# final_project3.net
KiCad netlist of a schematic drawn in EAGLE
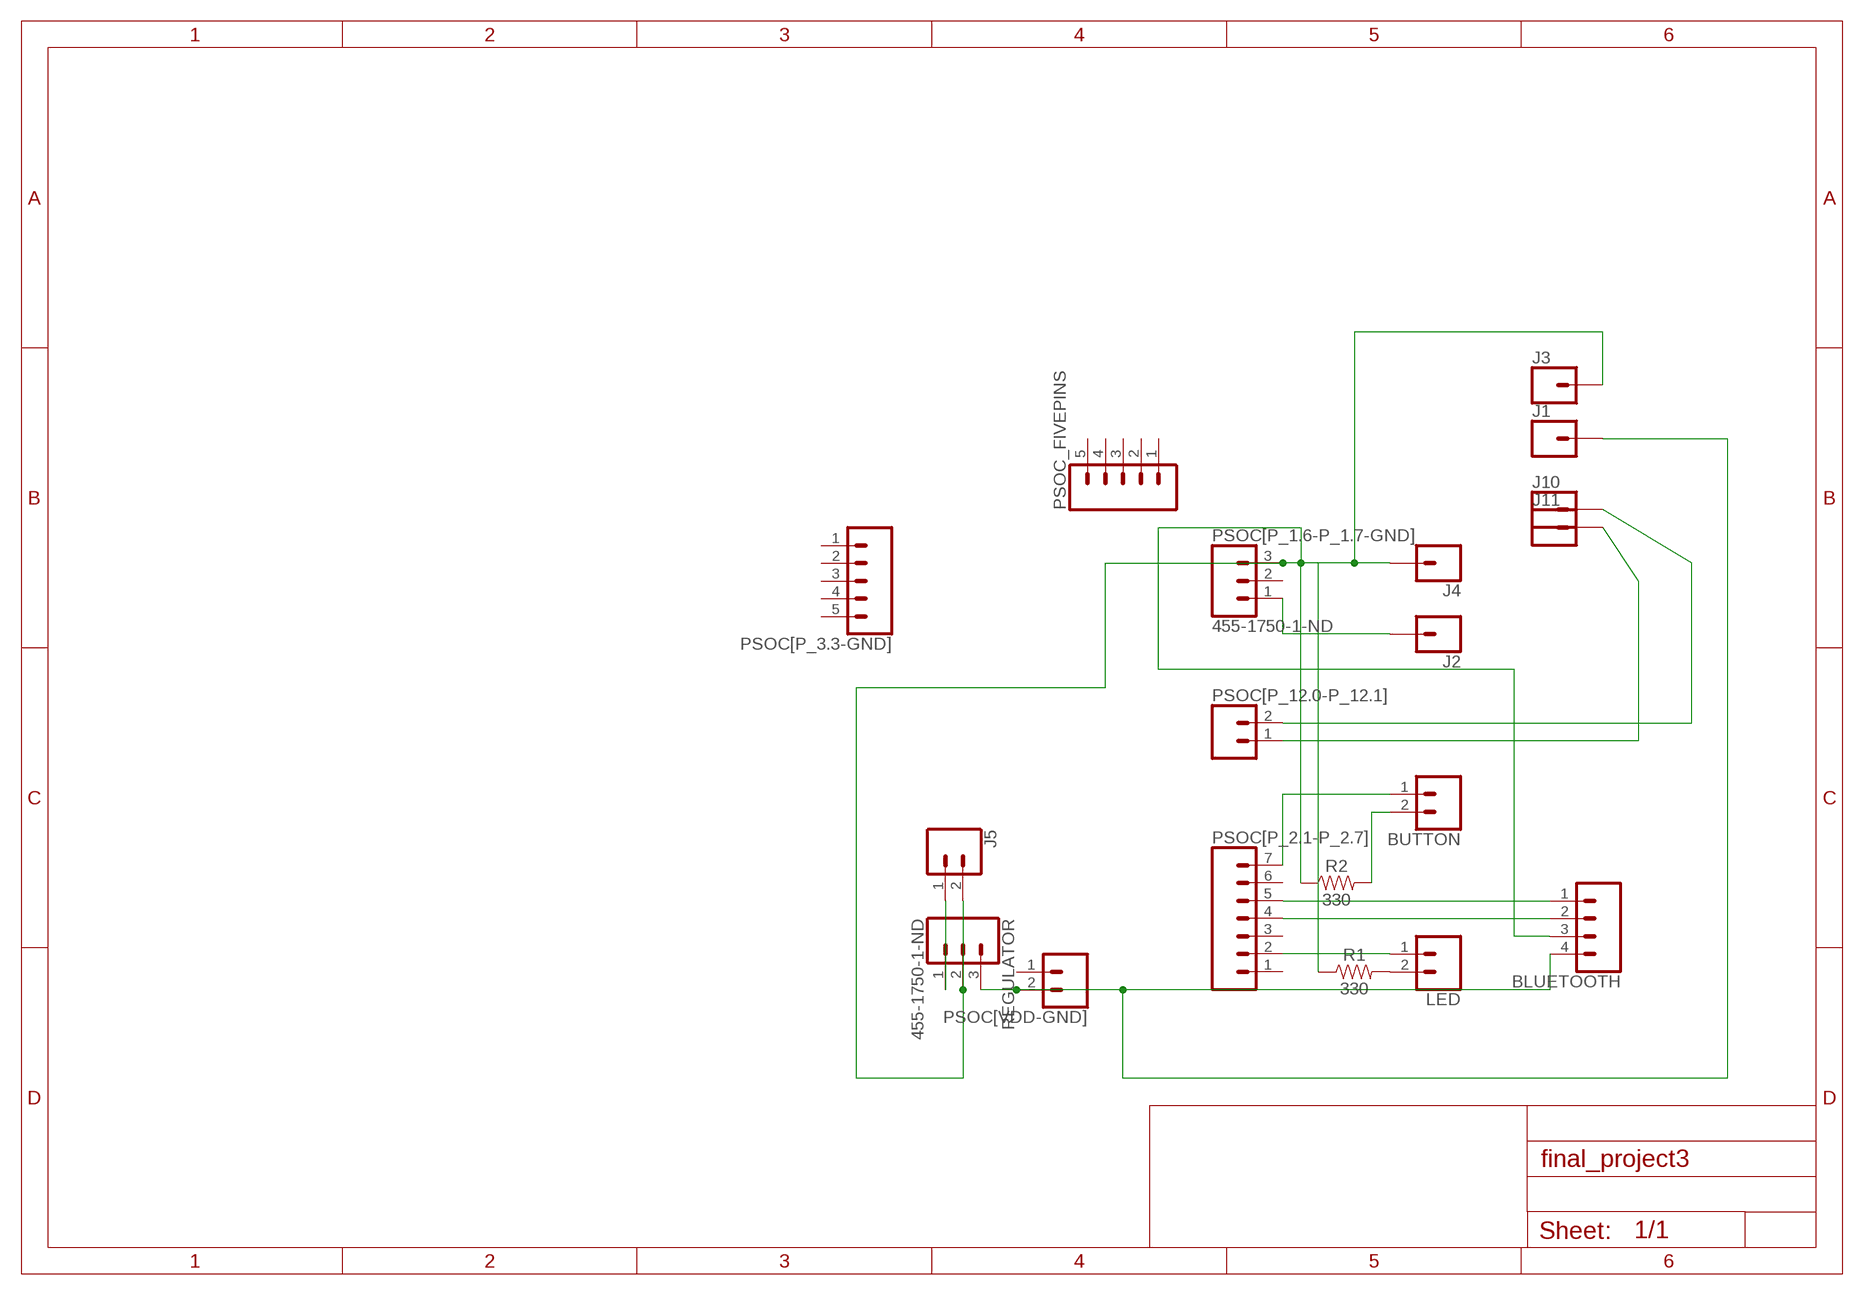
[diagram p0: schematic, sheet 1]

(export (version "E")
  (design (tool "Eeschema 10.0.6"))
  (components
    (comp (ref "BLUETOOTH")
      (value "CONN_04")
      (footprint "eagle-import:1X04")
      (libsource (lib "eagle-import") (part "CONN_04"))
    )
    (comp (ref "BUTTON")
      (value "CONN_02")
      (footprint "eagle-import:1X02")
      (libsource (lib "eagle-import") (part "CONN_02"))
    )
    (comp (ref "J1")
      (value "CONN_01")
      (footprint "eagle-import:1X01")
      (libsource (lib "eagle-import") (part "CONN_01"))
    )
    (comp (ref "J2")
      (value "CONN_01")
      (footprint "eagle-import:1X01")
      (libsource (lib "eagle-import") (part "CONN_01"))
    )
    (comp (ref "J3")
      (value "CONN_01")
      (footprint "eagle-import:1X01")
      (libsource (lib "eagle-import") (part "CONN_01"))
    )
    (comp (ref "J4")
      (value "CONN_01")
      (footprint "eagle-import:1X01")
      (libsource (lib "eagle-import") (part "CONN_01"))
    )
    (comp (ref "J5")
      (value "CONN_02")
      (footprint "eagle-import:1X02")
      (libsource (lib "eagle-import") (part "CONN_02"))
    )
    (comp (ref "J10")
      (value "CONN_01")
      (footprint "eagle-import:1X01")
      (libsource (lib "eagle-import") (part "CONN_01"))
    )
    (comp (ref "J11")
      (value "CONN_01")
      (footprint "eagle-import:1X01")
      (libsource (lib "eagle-import") (part "CONN_01"))
    )
    (comp (ref "LED")
      (value "CONN_02")
      (footprint "eagle-import:1X02")
      (libsource (lib "eagle-import") (part "CONN_02"))
    )
    (comp (ref "PSOC[P_1.6-P_1.7-GND]")
      (value "455-1750-1-ND")
      (footprint "eagle-import:1X03")
      (libsource (lib "eagle-import") (part "CONN_03"))
    )
    (comp (ref "PSOC[P_2.1-P_2.7]")
      (value "CONN_07")
      (footprint "eagle-import:1X07")
      (libsource (lib "eagle-import") (part "CONN_07"))
    )
    (comp (ref "PSOC[P_3.3-GND]")
      (value "CONN_05")
      (footprint "eagle-import:1X05")
      (libsource (lib "eagle-import") (part "CONN_05"))
    )
    (comp (ref "PSOC[P_12.0-P_12.1]")
      (value "CONN_02")
      (footprint "eagle-import:1X02")
      (libsource (lib "eagle-import") (part "CONN_02"))
    )
    (comp (ref "PSOC[VDD-GND]")
      (value "CONN_02")
      (footprint "eagle-import:1X02")
      (libsource (lib "eagle-import") (part "CONN_02"))
    )
    (comp (ref "PSOC_FIVEPINS")
      (value "CONN_05")
      (footprint "eagle-import:1X05")
      (libsource (lib "eagle-import") (part "CONN_05"))
    )
    (comp (ref "R1")
      (value "330")
      (footprint "eagle-import:AXIAL-0.3")
      (libsource (lib "eagle-import") (part "330OHM-HORIZ-1/10W-5%"))
    )
    (comp (ref "R2")
      (value "330")
      (footprint "eagle-import:AXIAL-0.3")
      (libsource (lib "eagle-import") (part "330OHM-HORIZ-1/10W-5%"))
    )
    (comp (ref "REGULATOR")
      (value "455-1750-1-ND")
      (footprint "eagle-import:1X03")
      (libsource (lib "eagle-import") (part "CONN_03"))
    )
  )
  (nets
    (net (code "1") (name "Net-(BLUETOOTH-Pad1)") (class "Default")
      (node (ref "BLUETOOTH") (pin "1") (pinfunction "1_1") (pintype "passive"))
      (node (ref "PSOC[P_2.1-P_2.7]") (pin "5") (pinfunction "5_5") (pintype "passive"))
    )
    (net (code "2") (name "Net-(BLUETOOTH-Pad2)") (class "Default")
      (node (ref "BLUETOOTH") (pin "2") (pinfunction "2_2") (pintype "passive"))
      (node (ref "PSOC[P_2.1-P_2.7]") (pin "4") (pinfunction "4_4") (pintype "passive"))
    )
    (net (code "3") (name "Net-(BLUETOOTH-Pad4)") (class "Default")
      (node (ref "BLUETOOTH") (pin "4") (pinfunction "4_4") (pintype "passive"))
      (node (ref "J1") (pin "1") (pinfunction "1_1") (pintype "passive"))
      (node (ref "PSOC[VDD-GND]") (pin "2") (pinfunction "2_2") (pintype "passive"))
      (node (ref "REGULATOR") (pin "3") (pinfunction "3_3") (pintype "passive"))
    )
    (net (code "4") (name "Net-(BUTTON-Pad1)") (class "Default")
      (node (ref "BUTTON") (pin "1") (pinfunction "1_1") (pintype "passive"))
      (node (ref "PSOC[P_2.1-P_2.7]") (pin "7") (pinfunction "7_7") (pintype "passive"))
    )
    (net (code "5") (name "Net-(J2-Pad1)") (class "Default")
      (node (ref "J2") (pin "1") (pinfunction "1_1") (pintype "passive"))
      (node (ref "PSOC[P_1.6-P_1.7-GND]") (pin "1") (pinfunction "1_1") (pintype "passive"))
    )
    (net (code "6") (name "Net-(J5-Pad1)") (class "Default")
      (node (ref "J5") (pin "1") (pinfunction "1_1") (pintype "passive"))
      (node (ref "REGULATOR") (pin "1") (pinfunction "1_1") (pintype "passive"))
    )
    (net (code "7") (name "Net-(J10-Pad1)") (class "Default")
      (node (ref "J10") (pin "1") (pinfunction "1_1") (pintype "passive"))
      (node (ref "PSOC[P_12.0-P_12.1]") (pin "2") (pinfunction "2_2") (pintype "passive"))
    )
    (net (code "8") (name "Net-(J11-Pad1)") (class "Default")
      (node (ref "J11") (pin "1") (pinfunction "1_1") (pintype "passive"))
      (node (ref "PSOC[P_12.0-P_12.1]") (pin "1") (pinfunction "1_1") (pintype "passive"))
    )
    (net (code "9") (name "Net-(LED-Pad1)") (class "Default")
      (node (ref "LED") (pin "1") (pinfunction "1_1") (pintype "passive"))
      (node (ref "PSOC[P_2.1-P_2.7]") (pin "2") (pinfunction "2_2") (pintype "passive"))
    )
    (net (code "10") (name "Net-(R1-1)") (class "Default")
      (node (ref "BLUETOOTH") (pin "3") (pinfunction "3_3") (pintype "passive"))
      (node (ref "J3") (pin "1") (pinfunction "1_1") (pintype "passive"))
      (node (ref "J4") (pin "1") (pinfunction "1_1") (pintype "passive"))
      (node (ref "J5") (pin "2") (pinfunction "2_2") (pintype "passive"))
      (node (ref "PSOC[P_1.6-P_1.7-GND]") (pin "3") (pinfunction "3_3") (pintype "passive"))
      (node (ref "R1") (pin "P$1") (pinfunction "1_P$1") (pintype "passive"))
      (node (ref "R2") (pin "P$1") (pinfunction "1_P$1") (pintype "passive"))
      (node (ref "REGULATOR") (pin "2") (pinfunction "2_2") (pintype "passive"))
    )
    (net (code "11") (name "Net-(R1-2)") (class "Default")
      (node (ref "LED") (pin "2") (pinfunction "2_2") (pintype "passive"))
      (node (ref "R1") (pin "P$2") (pinfunction "2_P$2") (pintype "passive"))
    )
    (net (code "12") (name "Net-(R2-2)") (class "Default")
      (node (ref "BUTTON") (pin "2") (pinfunction "2_2") (pintype "passive"))
      (node (ref "R2") (pin "P$2") (pinfunction "2_P$2") (pintype "passive"))
    )
    (net (code "13") (name "unconnected-(PSOC[P_1.6-P_1.7-GND]-Pad2)") (class "Default")
      (node (ref "PSOC[P_1.6-P_1.7-GND]") (pin "2") (pinfunction "2_2") (pintype "passive"))
    )
    (net (code "14") (name "unconnected-(PSOC[P_2.1-P_2.7]-Pad1)") (class "Default")
      (node (ref "PSOC[P_2.1-P_2.7]") (pin "1") (pinfunction "1_1") (pintype "passive"))
    )
    (net (code "15") (name "unconnected-(PSOC[P_2.1-P_2.7]-Pad3)") (class "Default")
      (node (ref "PSOC[P_2.1-P_2.7]") (pin "3") (pinfunction "3_3") (pintype "passive"))
    )
    (net (code "16") (name "unconnected-(PSOC[P_2.1-P_2.7]-Pad6)") (class "Default")
      (node (ref "PSOC[P_2.1-P_2.7]") (pin "6") (pinfunction "6_6") (pintype "passive"))
    )
    (net (code "17") (name "unconnected-(PSOC[P_3.3-GND]-Pad1)") (class "Default")
      (node (ref "PSOC[P_3.3-GND]") (pin "1") (pinfunction "1_1") (pintype "passive"))
    )
    (net (code "18") (name "unconnected-(PSOC[P_3.3-GND]-Pad2)") (class "Default")
      (node (ref "PSOC[P_3.3-GND]") (pin "2") (pinfunction "2_2") (pintype "passive"))
    )
    (net (code "19") (name "unconnected-(PSOC[P_3.3-GND]-Pad3)") (class "Default")
      (node (ref "PSOC[P_3.3-GND]") (pin "3") (pinfunction "3_3") (pintype "passive"))
    )
    (net (code "20") (name "unconnected-(PSOC[P_3.3-GND]-Pad4)") (class "Default")
      (node (ref "PSOC[P_3.3-GND]") (pin "4") (pinfunction "4_4") (pintype "passive"))
    )
    (net (code "21") (name "unconnected-(PSOC[P_3.3-GND]-Pad5)") (class "Default")
      (node (ref "PSOC[P_3.3-GND]") (pin "5") (pinfunction "5_5") (pintype "passive"))
    )
    (net (code "22") (name "unconnected-(PSOC[VDD-GND]-Pad1)") (class "Default")
      (node (ref "PSOC[VDD-GND]") (pin "1") (pinfunction "1_1") (pintype "passive"))
    )
    (net (code "23") (name "unconnected-(PSOC_FIVEPINS-Pad1)") (class "Default")
      (node (ref "PSOC_FIVEPINS") (pin "1") (pinfunction "1_1") (pintype "passive"))
    )
    (net (code "24") (name "unconnected-(PSOC_FIVEPINS-Pad2)") (class "Default")
      (node (ref "PSOC_FIVEPINS") (pin "2") (pinfunction "2_2") (pintype "passive"))
    )
    (net (code "25") (name "unconnected-(PSOC_FIVEPINS-Pad3)") (class "Default")
      (node (ref "PSOC_FIVEPINS") (pin "3") (pinfunction "3_3") (pintype "passive"))
    )
    (net (code "26") (name "unconnected-(PSOC_FIVEPINS-Pad4)") (class "Default")
      (node (ref "PSOC_FIVEPINS") (pin "4") (pinfunction "4_4") (pintype "passive"))
    )
    (net (code "27") (name "unconnected-(PSOC_FIVEPINS-Pad5)") (class "Default")
      (node (ref "PSOC_FIVEPINS") (pin "5") (pinfunction "5_5") (pintype "passive"))
    )
  )
)
